# CH1-Isolation.net
KiCad netlist of a schematic drawn in Altium Designer
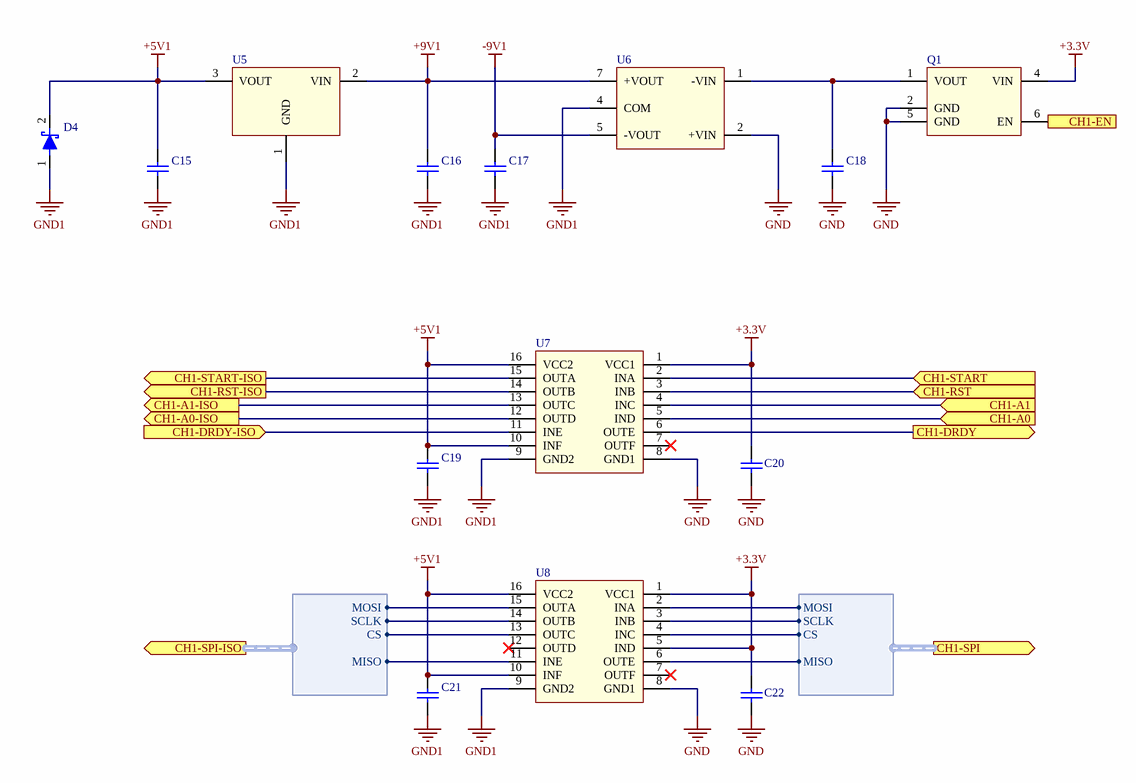
[diagram p0: CH1-Isolation.SchDoc]

(export (version "E")
  (design (tool "Eeschema 10.0.6"))
  (components
    (comp (ref "C15")
      (value "C0603C105M3RAC7867")
      (footprint "CAP-0603")
      (description "CAP CER 1uF 25V X7R 0603")
      (fields (field (name "MANUFACTURER") "Kemet") (field (name "TOLERANCE") "20%"))
      (libsource (lib "Kemet") (part "C0603C105M3RAC7867"))
    )
    (comp (ref "C16")
      (value "C0603C105M3RAC7867")
      (footprint "CAP-0603")
      (description "CAP CER 1uF 25V X7R 0603")
      (fields (field (name "MANUFACTURER") "Kemet") (field (name "TOLERANCE") "20%"))
      (libsource (lib "Kemet") (part "C0603C105M3RAC7867"))
    )
    (comp (ref "C17")
      (value "C0603C105M3RAC7867")
      (footprint "CAP-0603")
      (description "CAP CER 1uF 25V X7R 0603")
      (fields (field (name "MANUFACTURER") "Kemet") (field (name "TOLERANCE") "20%"))
      (libsource (lib "Kemet") (part "C0603C105M3RAC7867"))
    )
    (comp (ref "C18")
      (value "C0603C105M3RAC7867")
      (footprint "CAP-0603")
      (description "CAP CER 1uF 25V X7R 0603")
      (fields (field (name "MANUFACTURER") "Kemet") (field (name "TOLERANCE") "20%"))
      (libsource (lib "Kemet") (part "C0603C105M3RAC7867"))
    )
    (comp (ref "C19")
      (value "C0603C105M3RAC7867")
      (footprint "CAP-0603")
      (description "CAP CER 1uF 25V X7R 0603")
      (fields (field (name "MANUFACTURER") "Kemet") (field (name "TOLERANCE") "20%"))
      (libsource (lib "Kemet") (part "C0603C105M3RAC7867"))
    )
    (comp (ref "C20")
      (value "C0603C105M3RAC7867")
      (footprint "CAP-0603")
      (description "CAP CER 1uF 25V X7R 0603")
      (fields (field (name "MANUFACTURER") "Kemet") (field (name "TOLERANCE") "20%"))
      (libsource (lib "Kemet") (part "C0603C105M3RAC7867"))
    )
    (comp (ref "C21")
      (value "C0603C105M3RAC7867")
      (footprint "CAP-0603")
      (description "CAP CER 1uF 25V X7R 0603")
      (fields (field (name "MANUFACTURER") "Kemet") (field (name "TOLERANCE") "20%"))
      (libsource (lib "Kemet") (part "C0603C105M3RAC7867"))
    )
    (comp (ref "C22")
      (value "C0603C105M3RAC7867")
      (footprint "CAP-0603")
      (description "CAP CER 1uF 25V X7R 0603")
      (fields (field (name "MANUFACTURER") "Kemet") (field (name "TOLERANCE") "20%"))
      (libsource (lib "Kemet") (part "C0603C105M3RAC7867"))
    )
    (comp (ref "D4")
      (value "~")
      (footprint "SOD323 - DIODE UNIDIR")
      (description "Schottky Diode 30V 200mA SOT323")
      (fields (field (name "MANUFACTURER") "OnSemiconductor"))
      (libsource (lib "OnSemiconductors") (part "MM3Z5V6T1G"))
    )
    (comp (ref "Q1")
      (value "~")
      (footprint "TSSOP6")
      (fields (field (name "MANUFACTURER") "Microchip"))
      (libsource (lib "Microchip") (part "MIC94092YC6-TR"))
    )
    (comp (ref "U5")
      (value "~")
      (footprint "SOT23-5")
      (description "IC REG LDO 0.5V 0.15A TSOT23-5")
      (fields (field (name "MANUFACTURER") "ON Semiconductor"))
      (libsource (lib "OnSemiconductors") (part "NCP716BCSN500T1G"))
    )
    (comp (ref "U6")
      (value "R1D-3.309/P")
      (footprint "RECOM-R1D")
      (description "DC DC CONVERTER +/-9V 1W")
      (fields (field (name "MANUFACTURER") "Recom"))
      (libsource (lib "Recom") (part "R1D-3.309/P"))
    )
    (comp (ref "U7")
      (value "~")
      (footprint "SSOP16")
      (description "Digital Isolator, six-channel, 4/2, 16-SSOP")
      (fields (field (name "MANUFACTURER") "Texas Instruments"))
      (libsource (lib "TexasInstruments") (part "ISO7762FDBQ"))
    )
    (comp (ref "U8")
      (value "~")
      (footprint "SSOP16")
      (description "Digital Isolator, six-channel, 4/2, 16-SSOP")
      (fields (field (name "MANUFACTURER") "Texas Instruments"))
      (libsource (lib "TexasInstruments") (part "ISO7762FDBQ"))
    )
  )
  (nets
    (net (code "3") (name "+3.3V") (class "Default")
      (node (ref "C20") (pin "2") (pinfunction "2_2") (pintype "passive"))
      (node (ref "C22") (pin "2") (pinfunction "2_2") (pintype "passive"))
      (node (ref "Q1") (pin "4") (pinfunction "VIN_4") (pintype "passive"))
      (node (ref "U7") (pin "1") (pinfunction "VCC1_1") (pintype "passive"))
      (node (ref "U8") (pin "1") (pinfunction "VCC1_1") (pintype "passive"))
      (node (ref "U8") (pin "5") (pinfunction "IND_5") (pintype "passive"))
    )
    (net (code "4") (name "+5V1") (class "Default")
      (node (ref "C15") (pin "2") (pinfunction "2_2") (pintype "passive"))
      (node (ref "C19") (pin "2") (pinfunction "2_2") (pintype "passive"))
      (node (ref "C21") (pin "2") (pinfunction "2_2") (pintype "passive"))
      (node (ref "D4") (pin "2") (pinfunction "K_2") (pintype "passive"))
      (node (ref "U5") (pin "3") (pinfunction "VOUT_3") (pintype "passive"))
      (node (ref "U7") (pin "10") (pinfunction "INF_10") (pintype "passive"))
      (node (ref "U7") (pin "16") (pinfunction "VCC2_16") (pintype "passive"))
      (node (ref "U8") (pin "10") (pinfunction "INF_10") (pintype "passive"))
      (node (ref "U8") (pin "16") (pinfunction "VCC2_16") (pintype "passive"))
    )
    (net (code "5") (name "+9V1") (class "Default")
      (node (ref "C16") (pin "2") (pinfunction "2_2") (pintype "passive"))
      (node (ref "U5") (pin "2") (pinfunction "VIN_2") (pintype "passive"))
      (node (ref "U6") (pin "7") (pinfunction "+VOUT_7") (pintype "passive"))
    )
    (net (code "6") (name "-9V1") (class "Default")
      (node (ref "C17") (pin "2") (pinfunction "2_2") (pintype "passive"))
      (node (ref "U6") (pin "5") (pinfunction "-VOUT_5") (pintype "passive"))
    )
    (net (code "7") (name "/CH1-A0") (class "Default")
      (node (ref "U7") (pin "5") (pinfunction "IND_5") (pintype "passive"))
    )
    (net (code "8") (name "/CH1-A0-ISO") (class "Default")
      (node (ref "U7") (pin "12") (pinfunction "OUTD_12") (pintype "passive"))
    )
    (net (code "9") (name "/CH1-A1") (class "Default")
      (node (ref "U7") (pin "4") (pinfunction "INC_4") (pintype "passive"))
    )
    (net (code "10") (name "/CH1-A1-ISO") (class "Default")
      (node (ref "U7") (pin "13") (pinfunction "OUTC_13") (pintype "passive"))
    )
    (net (code "11") (name "/CH1-DRDY") (class "Default")
      (node (ref "U7") (pin "6") (pinfunction "OUTE_6") (pintype "passive"))
    )
    (net (code "12") (name "/CH1-DRDY-ISO") (class "Default")
      (node (ref "U7") (pin "11") (pinfunction "INE_11") (pintype "passive"))
    )
    (net (code "13") (name "/CH1-EN") (class "Default")
      (node (ref "Q1") (pin "6") (pinfunction "EN_6") (pintype "passive"))
    )
    (net (code "14") (name "/CH1-RST") (class "Default")
      (node (ref "U7") (pin "3") (pinfunction "INB_3") (pintype "passive"))
    )
    (net (code "15") (name "/CH1-RST-ISO") (class "Default")
      (node (ref "U7") (pin "14") (pinfunction "OUTB_14") (pintype "passive"))
    )
    (net (code "16") (name "/CH1-START") (class "Default")
      (node (ref "U7") (pin "2") (pinfunction "INA_2") (pintype "passive"))
    )
    (net (code "17") (name "/CH1-START-ISO") (class "Default")
      (node (ref "U7") (pin "15") (pinfunction "OUTA_15") (pintype "passive"))
    )
    (net (code "20") (name "GND") (class "Default")
      (node (ref "C18") (pin "1") (pinfunction "1_1") (pintype "passive"))
      (node (ref "C20") (pin "1") (pinfunction "1_1") (pintype "passive"))
      (node (ref "C22") (pin "1") (pinfunction "1_1") (pintype "passive"))
      (node (ref "Q1") (pin "2") (pinfunction "GND_2") (pintype "passive"))
      (node (ref "Q1") (pin "5") (pinfunction "GND_5") (pintype "passive"))
      (node (ref "U6") (pin "2") (pinfunction "+VIN_2") (pintype "passive"))
      (node (ref "U7") (pin "8") (pinfunction "GND1_8") (pintype "passive"))
      (node (ref "U8") (pin "8") (pinfunction "GND1_8") (pintype "passive"))
    )
    (net (code "21") (name "GND1") (class "Default")
      (node (ref "C15") (pin "1") (pinfunction "1_1") (pintype "passive"))
      (node (ref "C16") (pin "1") (pinfunction "1_1") (pintype "passive"))
      (node (ref "C17") (pin "1") (pinfunction "1_1") (pintype "passive"))
      (node (ref "C19") (pin "1") (pinfunction "1_1") (pintype "passive"))
      (node (ref "C21") (pin "1") (pinfunction "1_1") (pintype "passive"))
      (node (ref "D4") (pin "1") (pinfunction "A_1") (pintype "passive"))
      (node (ref "U5") (pin "1") (pinfunction "GND_1") (pintype "passive"))
      (node (ref "U6") (pin "4") (pinfunction "COM_4") (pintype "passive"))
      (node (ref "U7") (pin "9") (pinfunction "GND2_9") (pintype "passive"))
      (node (ref "U8") (pin "9") (pinfunction "GND2_9") (pintype "passive"))
    )
    (net (code "22") (name "Net-(Q1-VOUT)") (class "Default")
      (node (ref "C18") (pin "2") (pinfunction "2_2") (pintype "passive"))
      (node (ref "Q1") (pin "1") (pinfunction "VOUT_1") (pintype "passive"))
      (node (ref "U6") (pin "1") (pinfunction "-VIN_1") (pintype "passive"))
    )
    (net (code "23") (name "unconnected-(U7-OUTF-Pad7)") (class "Default")
      (node (ref "U7") (pin "7") (pinfunction "OUTF_7") (pintype "passive+no_connect"))
    )
    (net (code "24") (name "unconnected-(U8-INA-Pad2)") (class "Default")
      (node (ref "U8") (pin "2") (pinfunction "INA_2") (pintype "passive"))
    )
    (net (code "25") (name "unconnected-(U8-INB-Pad3)") (class "Default")
      (node (ref "U8") (pin "3") (pinfunction "INB_3") (pintype "passive"))
    )
    (net (code "26") (name "unconnected-(U8-INC-Pad4)") (class "Default")
      (node (ref "U8") (pin "4") (pinfunction "INC_4") (pintype "passive"))
    )
    (net (code "27") (name "unconnected-(U8-INE-Pad11)") (class "Default")
      (node (ref "U8") (pin "11") (pinfunction "INE_11") (pintype "passive"))
    )
    (net (code "28") (name "unconnected-(U8-OUTA-Pad15)") (class "Default")
      (node (ref "U8") (pin "15") (pinfunction "OUTA_15") (pintype "passive"))
    )
    (net (code "29") (name "unconnected-(U8-OUTB-Pad14)") (class "Default")
      (node (ref "U8") (pin "14") (pinfunction "OUTB_14") (pintype "passive"))
    )
    (net (code "30") (name "unconnected-(U8-OUTC-Pad13)") (class "Default")
      (node (ref "U8") (pin "13") (pinfunction "OUTC_13") (pintype "passive"))
    )
    (net (code "31") (name "unconnected-(U8-OUTD-Pad12)") (class "Default")
      (node (ref "U8") (pin "12") (pinfunction "OUTD_12") (pintype "passive+no_connect"))
    )
    (net (code "32") (name "unconnected-(U8-OUTE-Pad6)") (class "Default")
      (node (ref "U8") (pin "6") (pinfunction "OUTE_6") (pintype "passive"))
    )
    (net (code "33") (name "unconnected-(U8-OUTF-Pad7)") (class "Default")
      (node (ref "U8") (pin "7") (pinfunction "OUTF_7") (pintype "passive+no_connect"))
    )
  )
)
